# Level_Shifting.net
KiCad netlist of a schematic drawn in Altium Designer
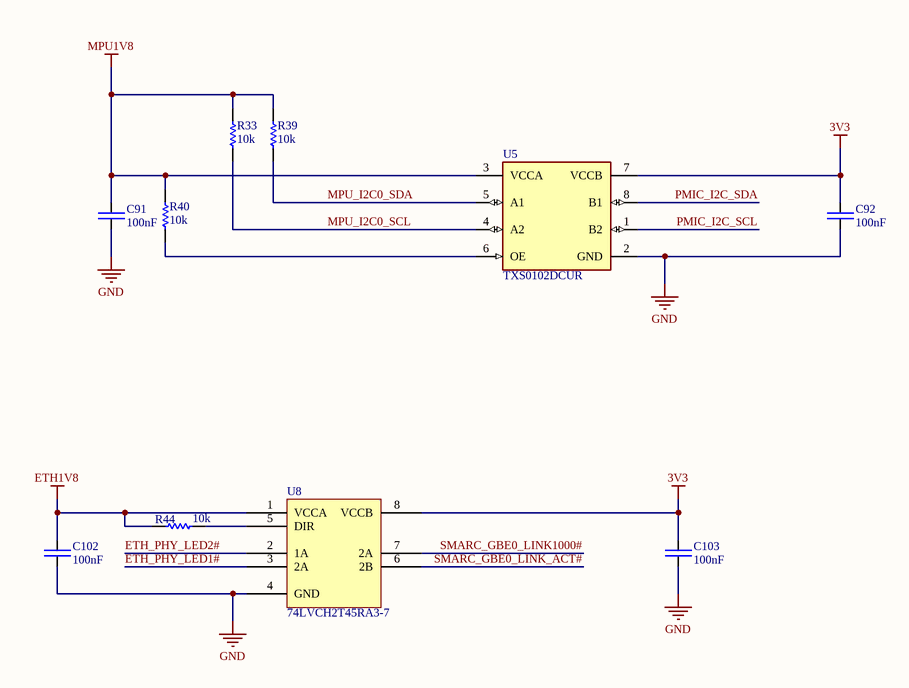
[diagram p0: Level Shifting.SchDoc]

(export (version "E")
  (design (tool "Eeschema 10.0.6"))
  (components
    (comp (ref "C91")
      (value "100nF")
      (footprint "CAP-0603")
      (description "Capacitor chip unpolarized. 0603")
      (libsource (lib "Master") (part "CAP-0603"))
    )
    (comp (ref "C92")
      (value "100nF")
      (footprint "CAP-0603")
      (description "Capacitor chip unpolarized. 0603")
      (libsource (lib "Master") (part "CAP-0603"))
    )
    (comp (ref "C102")
      (value "100nF")
      (footprint "CAP-0201")
      (description "Capacitor chip upolarized. 0201")
      (libsource (lib "Master") (part "CAP-0201"))
    )
    (comp (ref "C103")
      (value "100nF")
      (footprint "CAP-0201")
      (description "Capacitor chip upolarized. 0201")
      (libsource (lib "Master") (part "CAP-0201"))
    )
    (comp (ref "R33")
      (value "10k")
      (footprint "RES-0603")
      (description "Resistor chip. 0603")
      (libsource (lib "Master") (part "RES-0603"))
    )
    (comp (ref "R39")
      (value "10k")
      (footprint "RES-0603")
      (description "Resistor chip. 0603")
      (libsource (lib "Master") (part "RES-0603"))
    )
    (comp (ref "R40")
      (value "10k")
      (footprint "RES-0603")
      (description "Resistor chip. 0603")
      (libsource (lib "Master") (part "RES-0603"))
    )
    (comp (ref "R44")
      (value "10k")
      (footprint "RES-0201")
      (description "Resistor chip. 0201")
      (libsource (lib "Master") (part "RES-0201"))
    )
    (comp (ref "U5")
      (value "TXS0102DCUR")
      (footprint "FP-DCU0008A-MFG")
      (description "IC TRNSLTR BIDIRECTIONAL US8")
      (fields
        (field (name "MANUFACTURER") "Texas Instruments")
        (field (name "OCTOPART") "https://octopart.com/txs0102dcur-texas+instruments-5414308")
      )
      (libsource (lib "Altium Content Vault") (part "7edb3aeb21a89e92b7ef258fabac7d1"))
    )
    (comp (ref "U8")
      (value "74LVCH2T45RA3-7")
      (footprint "74LVCH2T45RA3-7")
      (description "Level shifter dual input bidirectional")
      (libsource (lib "Master") (part "74LVCH2T45RA3-7"))
    )
  )
  (nets
    (net (code "1") (name "/ETH_PHY_LED1#") (class "Default")
      (node (ref "U8") (pin "3") (pinfunction "2A_3") (pintype "passive"))
    )
    (net (code "2") (name "/ETH_PHY_LED2#") (class "Default")
      (node (ref "U8") (pin "2") (pinfunction "1A_2") (pintype "passive"))
    )
    (net (code "3") (name "/MPU_I2C0_SCL") (class "Default")
      (node (ref "R33") (pin "1") (pintype "passive"))
      (node (ref "U5") (pin "4") (pinfunction "A2_4") (pintype "bidirectional"))
    )
    (net (code "4") (name "/MPU_I2C0_SDA") (class "Default")
      (node (ref "R39") (pin "1") (pintype "passive"))
      (node (ref "U5") (pin "5") (pinfunction "A1_5") (pintype "bidirectional"))
    )
    (net (code "5") (name "/PMIC_I2C_SCL") (class "Default")
      (node (ref "U5") (pin "1") (pinfunction "B2_1") (pintype "bidirectional"))
    )
    (net (code "6") (name "/PMIC_I2C_SDA") (class "Default")
      (node (ref "U5") (pin "8") (pinfunction "B1_8") (pintype "bidirectional"))
    )
    (net (code "7") (name "/SMARC_GBE0_LINK1000#") (class "Default")
      (node (ref "U8") (pin "7") (pinfunction "2A_7") (pintype "passive"))
    )
    (net (code "8") (name "/SMARC_GBE0_LINK_ACT#") (class "Default")
      (node (ref "U8") (pin "6") (pinfunction "2B_6") (pintype "passive"))
    )
    (net (code "9") (name "3V3") (class "Default")
      (node (ref "C103") (pin "2") (pintype "passive"))
      (node (ref "C92") (pin "2") (pintype "passive"))
      (node (ref "U5") (pin "7") (pinfunction "VCCB_7") (pintype "power_in"))
      (node (ref "U8") (pin "8") (pinfunction "VCCB_8") (pintype "passive"))
    )
    (net (code "10") (name "ETH1V8") (class "Default")
      (node (ref "C102") (pin "2") (pintype "passive"))
      (node (ref "R44") (pin "1") (pintype "passive"))
      (node (ref "U8") (pin "1") (pinfunction "VCCA_1") (pintype "passive"))
    )
    (net (code "11") (name "GND") (class "Default")
      (node (ref "C102") (pin "1") (pintype "passive"))
      (node (ref "C103") (pin "1") (pintype "passive"))
      (node (ref "C91") (pin "1") (pintype "passive"))
      (node (ref "C92") (pin "1") (pintype "passive"))
      (node (ref "U5") (pin "2") (pinfunction "GND_2") (pintype "power_in"))
      (node (ref "U8") (pin "4") (pinfunction "GND_4") (pintype "passive"))
    )
    (net (code "12") (name "MPU1V8") (class "Default")
      (node (ref "C91") (pin "2") (pintype "passive"))
      (node (ref "R33") (pin "2") (pintype "passive"))
      (node (ref "R39") (pin "2") (pintype "passive"))
      (node (ref "R40") (pin "2") (pintype "passive"))
      (node (ref "U5") (pin "3") (pinfunction "VCCA_3") (pintype "power_in"))
    )
    (net (code "13") (name "Net-(U5-OE)") (class "Default")
      (node (ref "R40") (pin "1") (pintype "passive"))
      (node (ref "U5") (pin "6") (pinfunction "OE_6") (pintype "input"))
    )
    (net (code "14") (name "Net-(U8-DIR)") (class "Default")
      (node (ref "R44") (pin "2") (pintype "passive"))
      (node (ref "U8") (pin "5") (pinfunction "DIR_5") (pintype "passive"))
    )
  )
)
